# FingerMiddle.net
KiCad netlist of a schematic drawn in Altium Designer
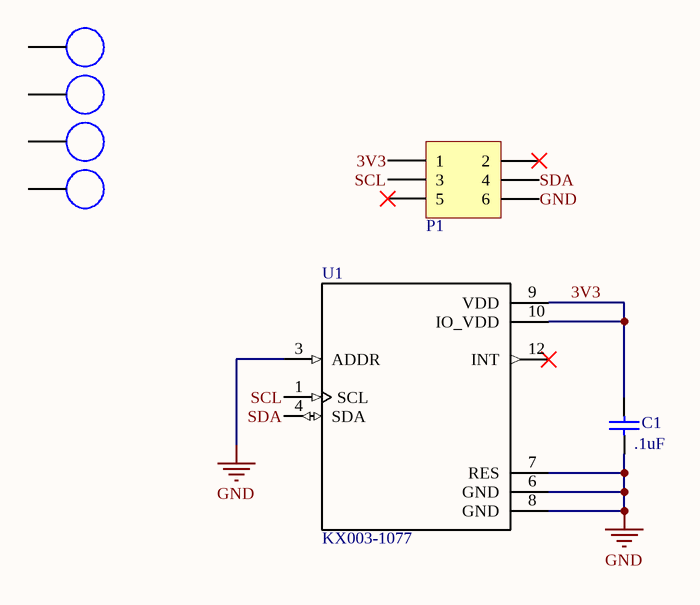
[diagram p0: FingerMiddle.SchDoc]

(export (version "E")
  (design (tool "Eeschema 10.0.6"))
  (components
    (comp (ref "C1")
      (value ".1uF")
      (footprint "0805")
      (description ".1, 10%, 50V")
      (fields (field (name "GFUPARTNO") "CL21A475KPFNNNE"))
      (libsource (lib "AltiumGFU64") (part "Cap"))
    )
    (comp (ref "DR1")
      (value "4-40 DRILL HOLE")
      (footprint "4_40 DRILL HOLE")
      (description "Mounting hole for 4-40 screw, non-BOM")
      (fields (field (name "GFUPARTNO") "4_40 DRILL HOLE"))
      (libsource (lib "AltiumGFU64") (part "8_32 DRILL HOLE"))
    )
    (comp (ref "DR2")
      (value "4-40 DRILL HOLE")
      (footprint "4_40 DRILL HOLE")
      (description "Mounting hole for 4-40 screw, non-BOM")
      (fields (field (name "GFUPARTNO") "4_40 DRILL HOLE"))
      (libsource (lib "AltiumGFU64") (part "8_32 DRILL HOLE"))
    )
    (comp (ref "DR3")
      (value "4-40 DRILL HOLE")
      (footprint "4_40 DRILL HOLE")
      (description "Mounting hole for 4-40 screw, non-BOM")
      (fields (field (name "GFUPARTNO") "4_40 DRILL HOLE"))
      (libsource (lib "AltiumGFU64") (part "8_32 DRILL HOLE"))
    )
    (comp (ref "DR4")
      (value "4-40 DRILL HOLE")
      (footprint "4_40 DRILL HOLE")
      (description "Mounting hole for 4-40 screw, non-BOM")
      (fields (field (name "GFUPARTNO") "4_40 DRILL HOLE"))
      (libsource (lib "AltiumGFU64") (part "8_32 DRILL HOLE"))
    )
    (comp (ref "P1")
      (value "90131-0123")
      (footprint "HDR2X3")
      (description "MOLEX CONN HEADER 6POS 2ROW .100\" STR TIN")
      (libsource (lib "AltiumGFU64") (part "Header 3X2"))
    )
    (comp (ref "U1")
      (value "KX003-1077")
      (footprint "*XDCR_KX003-1077")
      (description "Accelerometer X, Y, Z Axis Â±2g, 4g, 8g, 16g 3.5kHz _X,Y_, 1.8kHz _Z_ 12-LGA _2x2_")
      (fields
        (field (name "DIGI-KEY_PART_NUMBER") "KX003-1077CT-ND")
        (field (name "MF") "Rohm Semiconductor")
      )
      (libsource (lib "KX003-1077") (part "KX003-1077"))
    )
  )
  (nets
    (net (code "1") (name "/3V3") (class "Default")
      (node (ref "C1") (pin "2") (pinfunction "2_2") (pintype "passive"))
      (node (ref "P1") (pin "1") (pinfunction "1_1") (pintype "passive"))
      (node (ref "U1") (pin "10") (pinfunction "IO_VDD_10") (pintype "power_in"))
      (node (ref "U1") (pin "9") (pinfunction "VDD_9") (pintype "power_in"))
    )
    (net (code "2") (name "/SCL") (class "Default")
      (node (ref "P1") (pin "3") (pinfunction "3_3") (pintype "passive"))
      (node (ref "U1") (pin "1") (pinfunction "SCL_1") (pintype "input"))
    )
    (net (code "3") (name "/SDA") (class "Default")
      (node (ref "P1") (pin "4") (pinfunction "4_4") (pintype "passive"))
      (node (ref "U1") (pin "4") (pinfunction "SDA_4") (pintype "bidirectional"))
    )
    (net (code "4") (name "GND") (class "Default")
      (node (ref "C1") (pin "1") (pinfunction "1_1") (pintype "passive"))
      (node (ref "P1") (pin "6") (pinfunction "6_6") (pintype "passive"))
      (node (ref "U1") (pin "3") (pinfunction "ADDR_3") (pintype "input"))
      (node (ref "U1") (pin "6") (pinfunction "GND_6") (pintype "power_in"))
      (node (ref "U1") (pin "7") (pinfunction "RES_7") (pintype "power_in"))
      (node (ref "U1") (pin "8") (pinfunction "GND_8") (pintype "power_in"))
    )
    (net (code "5") (name "unconnected-(DR1-Pad0)") (class "Default")
      (node (ref "DR1") (pin "0") (pinfunction "0_0") (pintype "passive"))
    )
    (net (code "6") (name "unconnected-(DR2-Pad0)") (class "Default")
      (node (ref "DR2") (pin "0") (pinfunction "0_0") (pintype "passive"))
    )
    (net (code "7") (name "unconnected-(DR3-Pad0)") (class "Default")
      (node (ref "DR3") (pin "0") (pinfunction "0_0") (pintype "passive"))
    )
    (net (code "8") (name "unconnected-(DR4-Pad0)") (class "Default")
      (node (ref "DR4") (pin "0") (pinfunction "0_0") (pintype "passive"))
    )
    (net (code "9") (name "unconnected-(P1-Pad2)") (class "Default")
      (node (ref "P1") (pin "2") (pinfunction "2_2") (pintype "passive+no_connect"))
    )
    (net (code "10") (name "unconnected-(P1-Pad5)") (class "Default")
      (node (ref "P1") (pin "5") (pinfunction "5_5") (pintype "passive+no_connect"))
    )
    (net (code "11") (name "unconnected-(U1-INT-Pad12)") (class "Default")
      (node (ref "U1") (pin "12") (pinfunction "INT_12") (pintype "output+no_connect"))
    )
  )
)
